# 10-multimodal-microcontroller-rf.net
KiCad netlist of a schematic drawn in Altium Designer
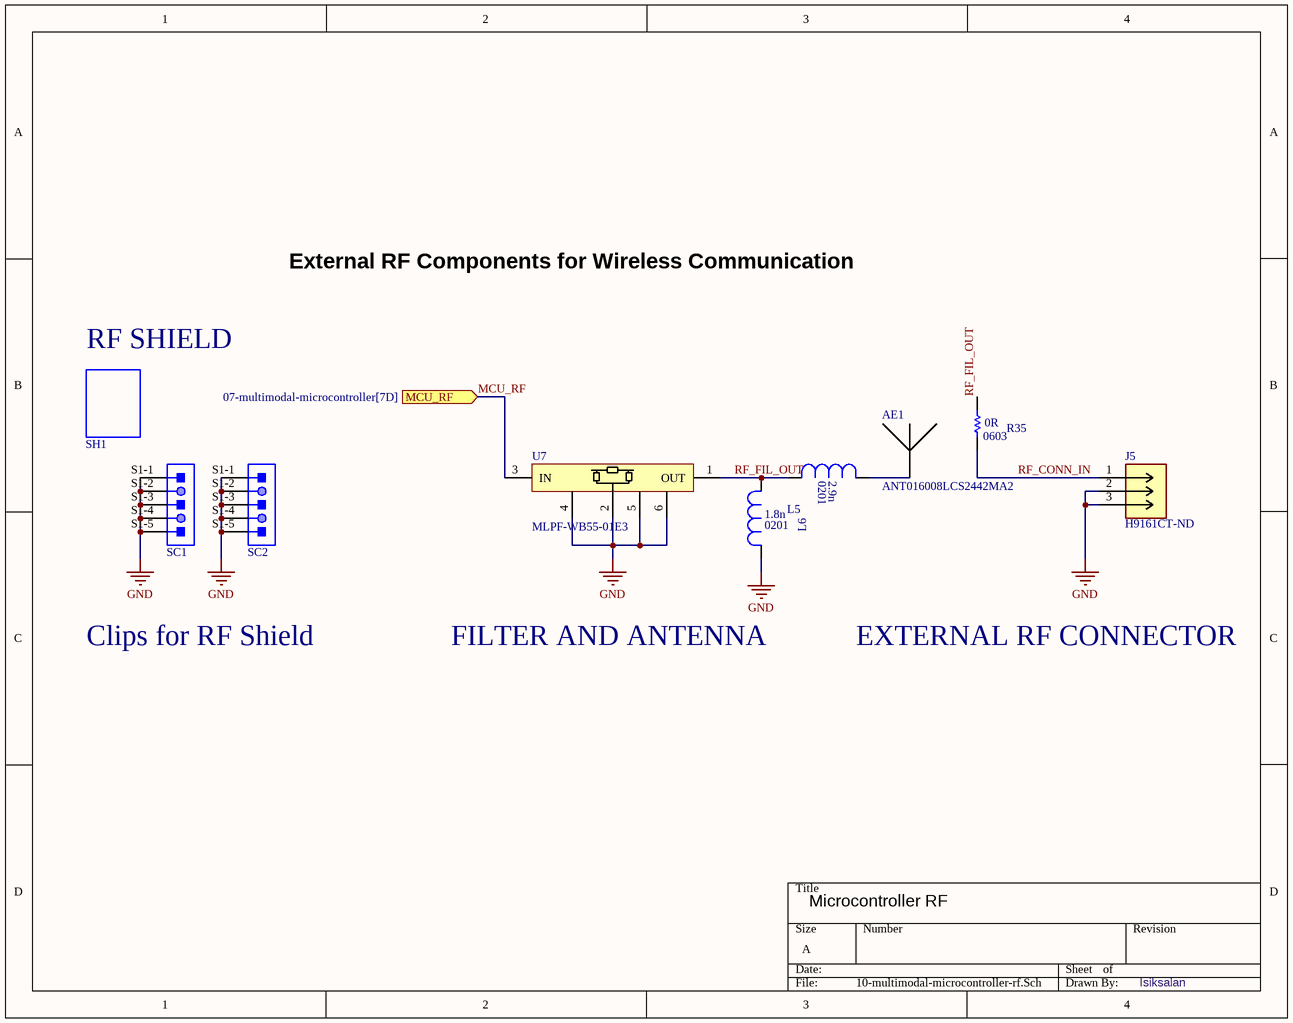
[diagram p0: 10-multimodal-microcontroller-rf.SchDoc]

(export (version "E")
  (design (tool "Eeschema 10.0.6"))
  (components
    (comp (ref "AE1")
      (value "ANT016008LCS2442MA2")
      (footprint "ANTENNA")
      (description "TDK - ANT016008LCS2442MA2 - Chip Antenna, ISM, 2.442 GHz, 50 Ohm, 1.6mm x 0.8mm x 0.4mm")
      (fields (field (name "MANUFACTURER") "TDK"))
      (libsource (lib "multimodal") (part "ANT016008LCS2442MA2"))
    )
    (comp (ref "J5")
      (value "U.FL-R-SMT(10)")
      (footprint "RF-CONNECTOR")
      (description "CONN U.FL RCPT STR 50 OHM SMD")
      (fields
        (field (name "MANUFACTURER") "Hirose")
        (field (name "SUPPLIER PART NUMBER 1") "H9161CT-ND")
        (field (name "COPYRIGHT") "Copyright (C) 2021 Ultra Librarian. All rights reserved.")
      )
      (libsource (lib "multimodal") (part "U.FL-R-SMT(10)"))
    )
    (comp (ref "L5")
      (value "MLG0603P1N8CT000")
      (footprint "INDTDK0201")
      (description "FIXED IND 1.8NH 700MA 100MOHM SM")
      (libsource (lib "multimodal") (part "MLG0603P1N8CT000"))
    )
    (comp (ref "L6")
      (value "MHQ0603P2N9ST000")
      (footprint "INDTDK0201")
      (description "FIXED IND 2.9NH 450MA 300MOHM SM")
      (libsource (lib "multimodal") (part "MHQ0603P2N9ST000"))
    )
    (comp (ref "R35")
      (value "RMCF0603ZT0R00")
      (footprint "RES-STACK-POLE-0603")
      (description "RES 0 OHM JUMPER 1/10W 0603")
      (libsource (lib "multimodal") (part "RMCF0603ZT0R00"))
    )
    (comp (ref "SC1")
      (value "S0951-46R")
      (footprint "RF-SHIELD+CLIP")
      (description "RFI SHIELD CLIP MINI TIN SMD")
      (libsource (lib "multimodal") (part "S0951-46R"))
    )
    (comp (ref "SC2")
      (value "S0951-46R")
      (footprint "RF-SHIELD+CLIP")
      (description "RFI SHIELD CLIP MINI TIN SMD")
      (libsource (lib "multimodal") (part "S0951-46R"))
    )
    (comp (ref "SH1")
      (value "MS190-10C")
      (description "RF SHLD COVER 0.563\"X0.764\" SNAP")
      (libsource (lib "multimodal") (part "MS190-10C"))
    )
    (comp (ref "U7")
      (value "MLPF-WB55-01E3")
      (footprint "Matched-Filter-2.4GHz")
      (description "2.4 GHz Matched filter companion chip for STM32WB55Cx and STM32WB55Rx")
      (fields (field (name "MANUFACTURER") "STMicroelectronics"))
      (libsource (lib "multimodal") (part "MLPF-WB55-01E3"))
    )
  )
  (nets
    (net (code "1") (name "/MCU_RF") (class "Default")
      (node (ref "U7") (pin "3") (pinfunction "IN_3") (pintype "passive"))
    )
    (net (code "2") (name "/RF_CONN_IN") (class "Default")
      (node (ref "J5") (pin "1") (pinfunction "1_1") (pintype "passive"))
      (node (ref "R35") (pin "1") (pinfunction "1_1") (pintype "passive"))
    )
    (net (code "3") (name "/RF_FIL_OUT") (class "Default")
      (node (ref "L5") (pin "1") (pinfunction "1_1") (pintype "passive"))
      (node (ref "L6") (pin "2") (pinfunction "2_2") (pintype "passive"))
      (node (ref "R35") (pin "2") (pinfunction "2_2") (pintype "passive"))
      (node (ref "U7") (pin "1") (pinfunction "OUT_1") (pintype "passive"))
    )
    (net (code "4") (name "GND") (class "Default")
      (node (ref "J5") (pin "2") (pinfunction "2_2") (pintype "passive"))
      (node (ref "J5") (pin "3") (pinfunction "3_3") (pintype "passive"))
      (node (ref "L5") (pin "2") (pinfunction "2_2") (pintype "passive"))
      (node (ref "SC1") (pin "S1-1") (pinfunction "S1-1_S1-1") (pintype "passive"))
      (node (ref "SC1") (pin "S1-2") (pinfunction "S1-2_S1-2") (pintype "passive"))
      (node (ref "SC1") (pin "S1-3") (pinfunction "S1-3_S1-3") (pintype "passive"))
      (node (ref "SC1") (pin "S1-4") (pinfunction "S1-4_S1-4") (pintype "passive"))
      (node (ref "SC1") (pin "S1-5") (pinfunction "S1-5_S1-5") (pintype "passive"))
      (node (ref "SC2") (pin "S1-1") (pinfunction "S1-1_S1-1") (pintype "passive"))
      (node (ref "SC2") (pin "S1-2") (pinfunction "S1-2_S1-2") (pintype "passive"))
      (node (ref "SC2") (pin "S1-3") (pinfunction "S1-3_S1-3") (pintype "passive"))
      (node (ref "SC2") (pin "S1-4") (pinfunction "S1-4_S1-4") (pintype "passive"))
      (node (ref "SC2") (pin "S1-5") (pinfunction "S1-5_S1-5") (pintype "passive"))
      (node (ref "U7") (pin "2") (pinfunction "2_2") (pintype "passive"))
      (node (ref "U7") (pin "4") (pinfunction "4_4") (pintype "passive"))
      (node (ref "U7") (pin "5") (pinfunction "5_5") (pintype "passive"))
      (node (ref "U7") (pin "6") (pinfunction "6_6") (pintype "passive"))
    )
    (net (code "5") (name "Net-(AE1-Pad2)") (class "Default")
      (node (ref "AE1") (pin "2") (pinfunction "2_2") (pintype "passive"))
      (node (ref "L6") (pin "1") (pinfunction "1_1") (pintype "passive"))
    )
  )
)
